# MRAM_MR25H40.net
KiCad netlist of a schematic drawn in Altium Designer
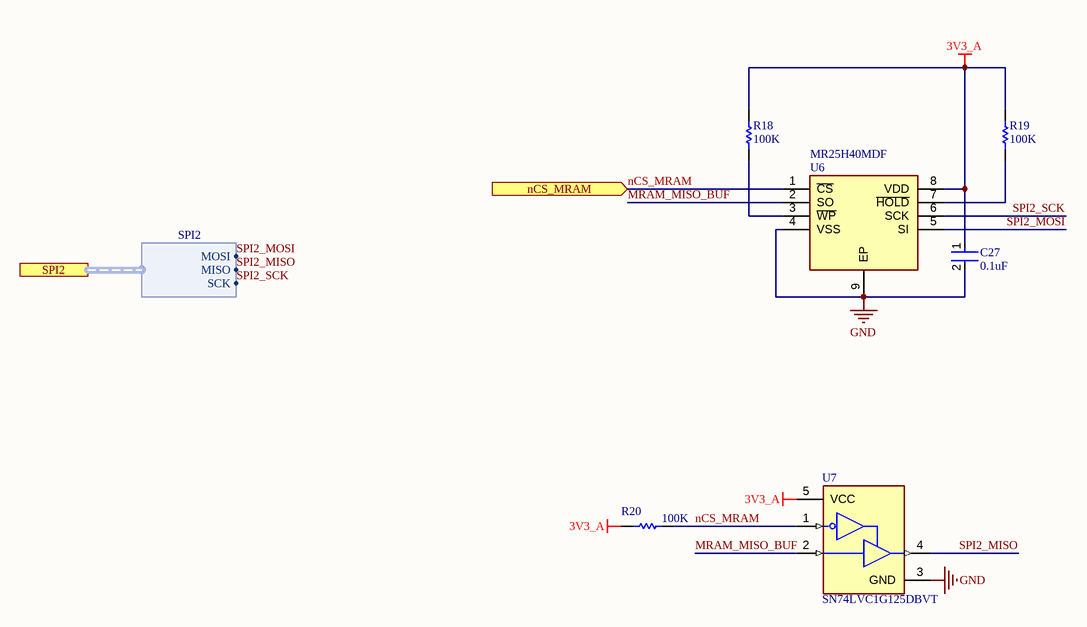
[diagram p0: MRAM_MR25H40.SchDoc]

(export (version "E")
  (design (tool "Eeschema 10.0.6"))
  (components
    (comp (ref "C27")
      (value "0.1uF")
      (footprint "FP-C0603C-CF-MFG")
      (description "CAP CER 0.1UF 50V X7R 0603")
      (fields (field (name "TOLERANCE") "0.1") (field (name "MANUFACTURER") "KEMET"))
      (libsource (lib "Altium Content Vault") (part "b4654b650e69147ec39a6b967a45e02"))
    )
    (comp (ref "R18")
      (value "100K")
      (footprint "RESC1608X55X30ML20T10")
      (fields (field (name "PART NUMBER") "RK73B1JTTD104J") (field (name "MANUFACTURER") "KOA Speer"))
      (libsource (lib "Altium Content Vault") (part "RES"))
    )
    (comp (ref "R19")
      (value "100K")
      (footprint "RESC1608X55X30ML20T10")
      (fields (field (name "PART NUMBER") "RK73B1JTTD104J") (field (name "MANUFACTURER") "KOA Speer"))
      (libsource (lib "Altium Content Vault") (part "RES"))
    )
    (comp (ref "R20")
      (value "100K")
      (footprint "RESC1608X55X30ML20T10")
      (fields (field (name "PART NUMBER") "RK73B1JTTD104J") (field (name "MANUFACTURER") "KOA Speer"))
      (libsource (lib "Altium Content Vault") (part "RES"))
    )
    (comp (ref "U6")
      (value "MR25H40MDF")
      (footprint "SamacSys:SON127P600X500X90-9N-D")
      (description "Integrated Circuit")
      (fields (field (name "MOUSER PART NUMBER") "936-MR25H40MDF"))
      (libsource (lib "*") (part "MR25H40MDF"))
    )
    (comp (ref "U7")
      (value "SN74LVC1G125DBVT")
      (footprint "FP-DBV0005A-MFG")
      (description "IC BUF NON-INVERT 5.5V SOT23-5")
      (fields
        (field (name "OCTOPART") "https://octopart.com/sn74lvc1g125dbvt-texas+instruments-1006799")
        (field (name "MANUFACTURER") "Texas Instruments")
      )
      (libsource (lib "Altium Content Vault") (part "58769f6d8490b1ac5b52b989db43374"))
    )
  )
  (nets
    (net (code "2") (name "/MRAM_MISO_BUF") (class "Default")
      (node (ref "U6") (pin "2") (pinfunction "SO_2") (pintype "passive"))
      (node (ref "U7") (pin "2") (pinfunction "A_2") (pintype "input"))
    )
    (net (code "3") (name "/SPI2_MISO") (class "Default")
      (node (ref "U7") (pin "4") (pinfunction "Y_4") (pintype "output"))
    )
    (net (code "4") (name "/SPI2_MOSI") (class "Default")
      (node (ref "U6") (pin "5") (pinfunction "SI_5") (pintype "passive"))
    )
    (net (code "5") (name "/SPI2_SCK") (class "Default")
      (node (ref "U6") (pin "6") (pinfunction "SCK_6") (pintype "passive"))
    )
    (net (code "6") (name "/nCS_MRAM") (class "Default")
      (node (ref "R20") (pin "1") (pinfunction "1_1") (pintype "passive"))
      (node (ref "U6") (pin "1") (pinfunction "~{CS}_1") (pintype "passive"))
      (node (ref "U7") (pin "1") (pinfunction "~{OE}_1") (pintype "input"))
    )
    (net (code "8") (name "3V3_A") (class "Default")
      (node (ref "C27") (pin "1") (pinfunction "1_1") (pintype "passive"))
      (node (ref "R18") (pin "1") (pinfunction "1_1") (pintype "passive"))
      (node (ref "R19") (pin "1") (pinfunction "1_1") (pintype "passive"))
      (node (ref "R20") (pin "2") (pinfunction "2_2") (pintype "passive"))
      (node (ref "U6") (pin "8") (pinfunction "VDD_8") (pintype "passive"))
      (node (ref "U7") (pin "5") (pinfunction "VCC_5") (pintype "power_in"))
    )
    (net (code "9") (name "GND") (class "Default")
      (node (ref "C27") (pin "2") (pinfunction "2_2") (pintype "passive"))
      (node (ref "U6") (pin "4") (pinfunction "VSS_4") (pintype "passive"))
      (node (ref "U6") (pin "9") (pinfunction "EP_9") (pintype "passive"))
      (node (ref "U7") (pin "3") (pinfunction "GND_3") (pintype "power_in"))
    )
    (net (code "10") (name "Net-(U6-~{HOLD})") (class "Default")
      (node (ref "R19") (pin "2") (pinfunction "2_2") (pintype "passive"))
      (node (ref "U6") (pin "7") (pinfunction "~{HOLD}_7") (pintype "passive"))
    )
    (net (code "11") (name "Net-(U6-~{WP})") (class "Default")
      (node (ref "R18") (pin "2") (pinfunction "2_2") (pintype "passive"))
      (node (ref "U6") (pin "3") (pinfunction "~{WP}_3") (pintype "passive"))
    )
  )
)
